# complete.net
KiCad netlist of a schematic drawn in EAGLE
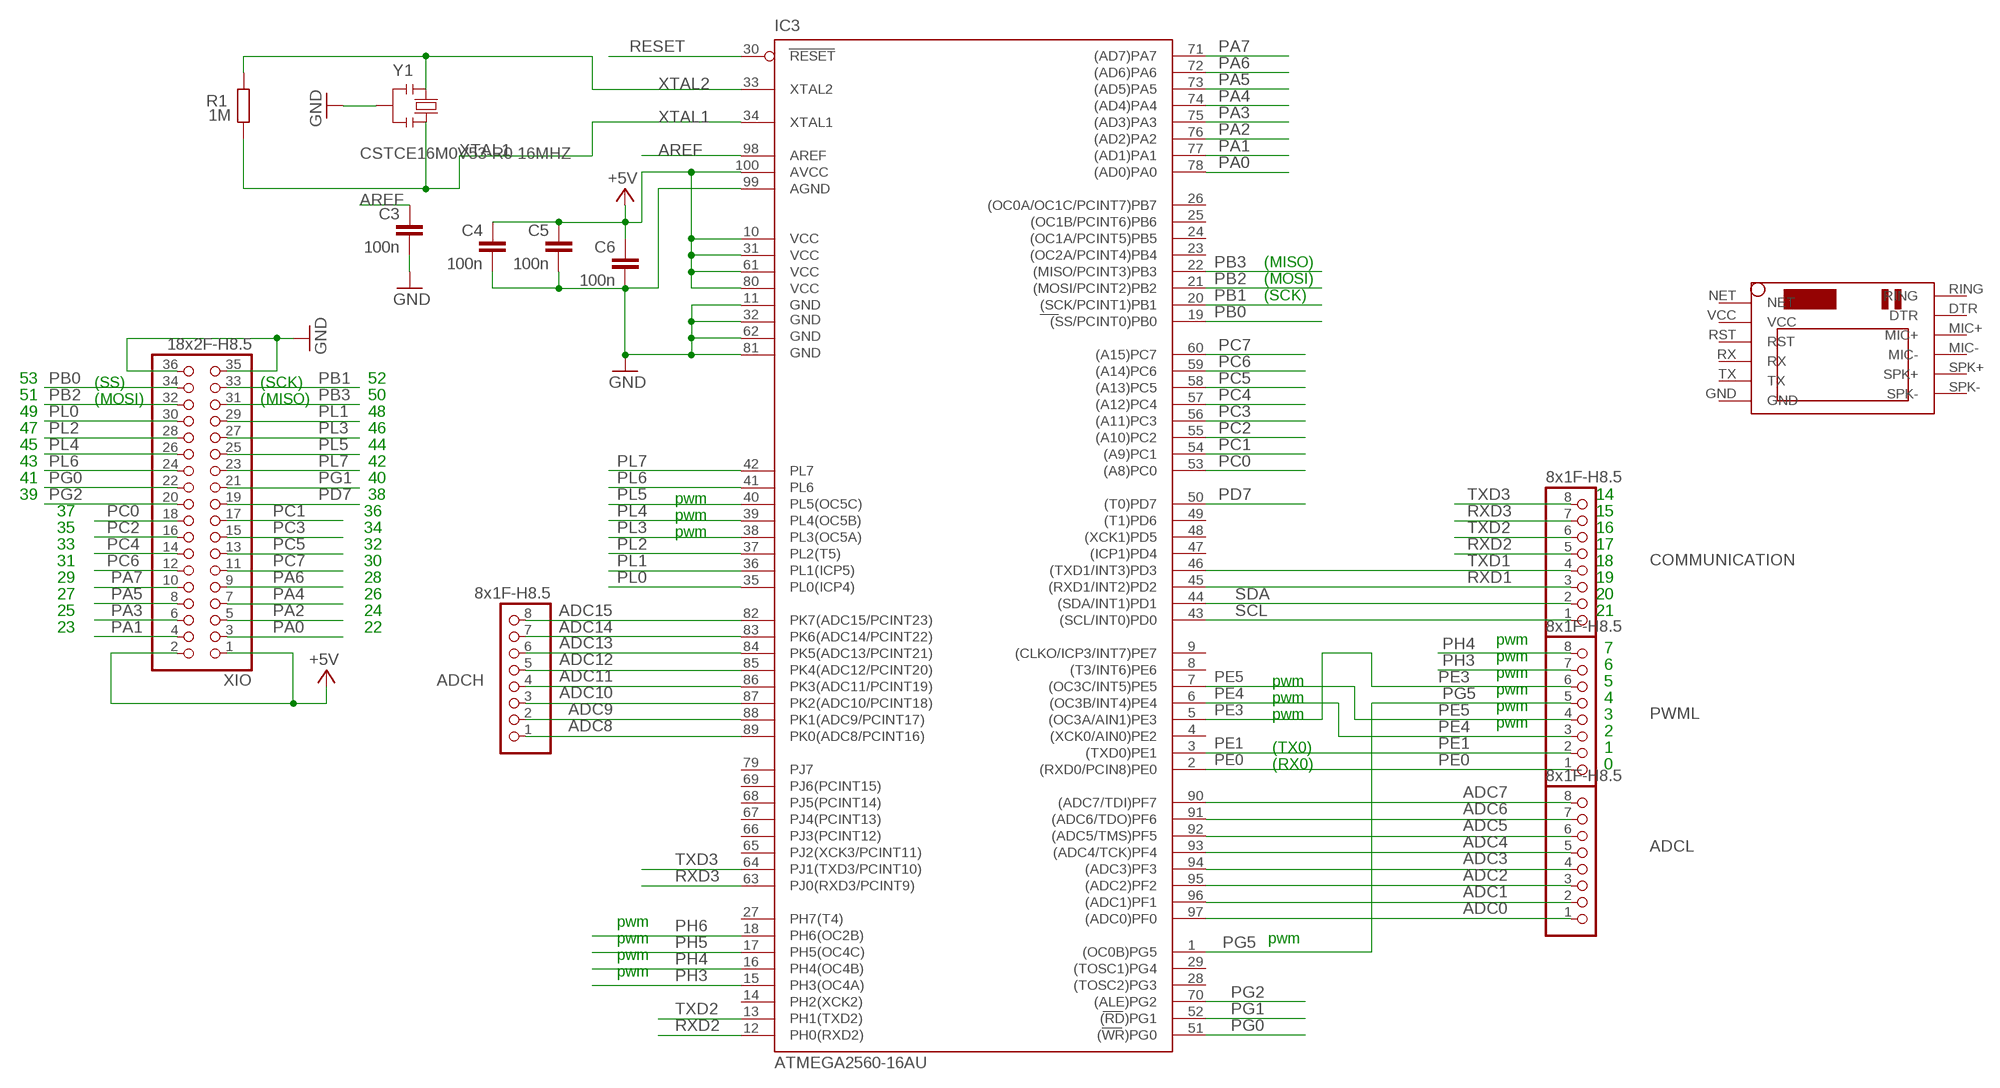
[diagram p0: schematic, sheet 1]

(export (version "E")
  (design (tool "Eeschema 10.0.6"))
  (components
    (comp (ref "ADCH")
      (value "8x1F-H8.5")
      (footprint "eagle-import:1X08")
      (libsource (lib "eagle-import") (part "PINHD-1X8"))
    )
    (comp (ref "ADCL")
      (value "8x1F-H8.5")
      (footprint "eagle-import:1X08")
      (libsource (lib "eagle-import") (part "PINHD-1X8"))
    )
    (comp (ref "C3")
      (value "100n")
      (footprint "eagle-import:C0603-ROUND")
      (libsource (lib "eagle-import") (part "C-EU0603-RND"))
    )
    (comp (ref "C4")
      (value "100n")
      (footprint "eagle-import:C0603-ROUND")
      (libsource (lib "eagle-import") (part "C-EU0603-RND"))
    )
    (comp (ref "C5")
      (value "100n")
      (footprint "eagle-import:C0603-ROUND")
      (libsource (lib "eagle-import") (part "C-EU0603-RND"))
    )
    (comp (ref "C6")
      (value "100n")
      (footprint "eagle-import:C0603-ROUND")
      (libsource (lib "eagle-import") (part "C-EU0603-RND"))
    )
    (comp (ref "COMMUNICATION")
      (value "8x1F-H8.5")
      (footprint "eagle-import:1X08")
      (libsource (lib "eagle-import") (part "PINHD-1X8"))
    )
    (comp (ref "IC3")
      (value "ATMEGA2560-16AU")
      (footprint "eagle-import:TQFP100")
      (libsource (lib "eagle-import") (part "ATMEGA2560AU2560-16"))
    )
    (comp (ref "PWML")
      (value "8x1F-H8.5")
      (footprint "eagle-import:1X08")
      (libsource (lib "eagle-import") (part "PINHD-1X8"))
    )
    (comp (ref "R1")
      (value "1M")
      (footprint "eagle-import:R0603-ROUND")
      (libsource (lib "eagle-import") (part "R-EU_R0603"))
    )
    (comp (ref "U$1")
      (value "SIM800LMODULE")
      (footprint "eagle-import:SIM800LMODULE")
      (libsource (lib "eagle-import") (part "SIM800LMODULE"))
    )
    (comp (ref "XIO")
      (value "18x2F-H8.5")
      (footprint "eagle-import:2X18")
      (libsource (lib "eagle-import") (part "PINHD-2X18"))
    )
    (comp (ref "Y1")
      (value "CSTCE16M0V53-R0 16MHZ")
      (footprint "eagle-import:RESONATOR")
      (libsource (lib "eagle-import") (part "RESONATORMU"))
    )
  )
  (nets
    (net (code "1") (name "+5V") (class "Default")
      (node (ref "C4") (pin "1") (pinfunction "1_1") (pintype "passive"))
      (node (ref "C5") (pin "1") (pinfunction "1_1") (pintype "passive"))
      (node (ref "C6") (pin "1") (pinfunction "1_1") (pintype "passive"))
      (node (ref "IC3") (pin "10") (pinfunction "VCC_10") (pintype "power_in"))
      (node (ref "IC3") (pin "100") (pinfunction "AVCC_100") (pintype "power_in"))
      (node (ref "IC3") (pin "31") (pinfunction "VCC1_31") (pintype "power_in"))
      (node (ref "IC3") (pin "61") (pinfunction "VCC2_61") (pintype "power_in"))
      (node (ref "IC3") (pin "80") (pinfunction "VCC3_80") (pintype "power_in"))
      (node (ref "XIO") (pin "1") (pinfunction "1_1") (pintype "passive"))
      (node (ref "XIO") (pin "2") (pinfunction "2_2") (pintype "passive"))
    )
    (net (code "2") (name "/ADC0") (class "Default")
      (node (ref "ADCL") (pin "1") (pinfunction "1_1") (pintype "passive"))
      (node (ref "IC3") (pin "97") (pinfunction "(ADC0)PF0_97") (pintype "bidirectional"))
    )
    (net (code "3") (name "/ADC1") (class "Default")
      (node (ref "ADCL") (pin "2") (pinfunction "2_2") (pintype "passive"))
      (node (ref "IC3") (pin "96") (pinfunction "(ADC1)PF1_96") (pintype "bidirectional"))
    )
    (net (code "4") (name "/ADC2") (class "Default")
      (node (ref "ADCL") (pin "3") (pinfunction "3_3") (pintype "passive"))
      (node (ref "IC3") (pin "95") (pinfunction "(ADC2)PF2_95") (pintype "bidirectional"))
    )
    (net (code "5") (name "/ADC3") (class "Default")
      (node (ref "ADCL") (pin "4") (pinfunction "4_4") (pintype "passive"))
      (node (ref "IC3") (pin "94") (pinfunction "(ADC3)PF3_94") (pintype "bidirectional"))
    )
    (net (code "6") (name "/ADC4") (class "Default")
      (node (ref "ADCL") (pin "5") (pinfunction "5_5") (pintype "passive"))
      (node (ref "IC3") (pin "93") (pinfunction "(ADC4/TCK)PF4_93") (pintype "bidirectional"))
    )
    (net (code "7") (name "/ADC5") (class "Default")
      (node (ref "ADCL") (pin "6") (pinfunction "6_6") (pintype "passive"))
      (node (ref "IC3") (pin "92") (pinfunction "(ADC5/TMS)PF5_92") (pintype "bidirectional"))
    )
    (net (code "8") (name "/ADC6") (class "Default")
      (node (ref "ADCL") (pin "7") (pinfunction "7_7") (pintype "passive"))
      (node (ref "IC3") (pin "91") (pinfunction "(ADC6/TDO)PF6_91") (pintype "bidirectional"))
    )
    (net (code "9") (name "/ADC7") (class "Default")
      (node (ref "ADCL") (pin "8") (pinfunction "8_8") (pintype "passive"))
      (node (ref "IC3") (pin "90") (pinfunction "(ADC7/TDI)PF7_90") (pintype "bidirectional"))
    )
    (net (code "10") (name "/ADC8") (class "Default")
      (node (ref "ADCH") (pin "1") (pinfunction "1_1") (pintype "passive"))
      (node (ref "IC3") (pin "89") (pinfunction "PK0(ADC8/PCINT16)_89") (pintype "bidirectional"))
    )
    (net (code "11") (name "/ADC9") (class "Default")
      (node (ref "ADCH") (pin "2") (pinfunction "2_2") (pintype "passive"))
      (node (ref "IC3") (pin "88") (pinfunction "PK1(ADC9/PCINT17)_88") (pintype "bidirectional"))
    )
    (net (code "12") (name "/ADC10") (class "Default")
      (node (ref "ADCH") (pin "3") (pinfunction "3_3") (pintype "passive"))
      (node (ref "IC3") (pin "87") (pinfunction "PK2(ADC10/PCINT18)_87") (pintype "bidirectional"))
    )
    (net (code "13") (name "/ADC11") (class "Default")
      (node (ref "ADCH") (pin "4") (pinfunction "4_4") (pintype "passive"))
      (node (ref "IC3") (pin "86") (pinfunction "PK3(ADC11/PCINT19)_86") (pintype "bidirectional"))
    )
    (net (code "14") (name "/ADC12") (class "Default")
      (node (ref "ADCH") (pin "5") (pinfunction "5_5") (pintype "passive"))
      (node (ref "IC3") (pin "85") (pinfunction "PK4(ADC12/PCINT20)_85") (pintype "bidirectional"))
    )
    (net (code "15") (name "/ADC13") (class "Default")
      (node (ref "ADCH") (pin "6") (pinfunction "6_6") (pintype "passive"))
      (node (ref "IC3") (pin "84") (pinfunction "PK5(ADC13/PCINT21)_84") (pintype "bidirectional"))
    )
    (net (code "16") (name "/ADC14") (class "Default")
      (node (ref "ADCH") (pin "7") (pinfunction "7_7") (pintype "passive"))
      (node (ref "IC3") (pin "83") (pinfunction "PK6(ADC14/PCINT22)_83") (pintype "bidirectional"))
    )
    (net (code "17") (name "/ADC15") (class "Default")
      (node (ref "ADCH") (pin "8") (pinfunction "8_8") (pintype "passive"))
      (node (ref "IC3") (pin "82") (pinfunction "PK7(ADC15/PCINT23)_82") (pintype "bidirectional"))
    )
    (net (code "18") (name "/AREF") (class "Default")
      (node (ref "C3") (pin "1") (pinfunction "1_1") (pintype "passive"))
      (node (ref "IC3") (pin "98") (pinfunction "AREF_98") (pintype "bidirectional"))
    )
    (net (code "19") (name "/PA0") (class "Default")
      (node (ref "IC3") (pin "78") (pinfunction "(AD0)PA0_78") (pintype "bidirectional"))
      (node (ref "XIO") (pin "3") (pinfunction "3_3") (pintype "passive"))
    )
    (net (code "20") (name "/PA1") (class "Default")
      (node (ref "IC3") (pin "77") (pinfunction "(AD1)PA1_77") (pintype "bidirectional"))
      (node (ref "XIO") (pin "4") (pinfunction "4_4") (pintype "passive"))
    )
    (net (code "21") (name "/PA2") (class "Default")
      (node (ref "IC3") (pin "76") (pinfunction "(AD2)PA2_76") (pintype "bidirectional"))
      (node (ref "XIO") (pin "5") (pinfunction "5_5") (pintype "passive"))
    )
    (net (code "22") (name "/PA3") (class "Default")
      (node (ref "IC3") (pin "75") (pinfunction "(AD3)PA3_75") (pintype "bidirectional"))
      (node (ref "XIO") (pin "6") (pinfunction "6_6") (pintype "passive"))
    )
    (net (code "23") (name "/PA4") (class "Default")
      (node (ref "IC3") (pin "74") (pinfunction "(AD4)PA4_74") (pintype "bidirectional"))
      (node (ref "XIO") (pin "7") (pinfunction "7_7") (pintype "passive"))
    )
    (net (code "24") (name "/PA5") (class "Default")
      (node (ref "IC3") (pin "73") (pinfunction "(AD5)PA5_73") (pintype "bidirectional"))
      (node (ref "XIO") (pin "8") (pinfunction "8_8") (pintype "passive"))
    )
    (net (code "25") (name "/PA6") (class "Default")
      (node (ref "IC3") (pin "72") (pinfunction "(AD6)PA6_72") (pintype "bidirectional"))
      (node (ref "XIO") (pin "9") (pinfunction "9_9") (pintype "passive"))
    )
    (net (code "26") (name "/PA7") (class "Default")
      (node (ref "IC3") (pin "71") (pinfunction "(AD7)PA7_71") (pintype "bidirectional"))
      (node (ref "XIO") (pin "10") (pinfunction "10_10") (pintype "passive"))
    )
    (net (code "27") (name "/PB0") (class "Default")
      (node (ref "IC3") (pin "19") (pinfunction "(SS/PCINT0)PB0_19") (pintype "bidirectional"))
      (node (ref "XIO") (pin "34") (pinfunction "34_34") (pintype "passive"))
    )
    (net (code "28") (name "/PB1") (class "Default")
      (node (ref "IC3") (pin "20") (pinfunction "(SCK/PCINT1)PB1_20") (pintype "bidirectional"))
      (node (ref "XIO") (pin "33") (pinfunction "33_33") (pintype "passive"))
    )
    (net (code "29") (name "/PB2") (class "Default")
      (node (ref "IC3") (pin "21") (pinfunction "(MOSI/PCINT2)PB2_21") (pintype "bidirectional"))
      (node (ref "XIO") (pin "32") (pinfunction "32_32") (pintype "passive"))
    )
    (net (code "30") (name "/PB3") (class "Default")
      (node (ref "IC3") (pin "22") (pinfunction "(MISO/PCINT3)PB3_22") (pintype "bidirectional"))
      (node (ref "XIO") (pin "31") (pinfunction "31_31") (pintype "passive"))
    )
    (net (code "31") (name "/PC0") (class "Default")
      (node (ref "IC3") (pin "53") (pinfunction "(A8)PC0_53") (pintype "bidirectional"))
      (node (ref "XIO") (pin "18") (pinfunction "18_18") (pintype "passive"))
    )
    (net (code "32") (name "/PC1") (class "Default")
      (node (ref "IC3") (pin "54") (pinfunction "(A9)PC1_54") (pintype "bidirectional"))
      (node (ref "XIO") (pin "17") (pinfunction "17_17") (pintype "passive"))
    )
    (net (code "33") (name "/PC2") (class "Default")
      (node (ref "IC3") (pin "55") (pinfunction "(A10)PC2_55") (pintype "bidirectional"))
      (node (ref "XIO") (pin "16") (pinfunction "16_16") (pintype "passive"))
    )
    (net (code "34") (name "/PC3") (class "Default")
      (node (ref "IC3") (pin "56") (pinfunction "(A11)PC3_56") (pintype "bidirectional"))
      (node (ref "XIO") (pin "15") (pinfunction "15_15") (pintype "passive"))
    )
    (net (code "35") (name "/PC4") (class "Default")
      (node (ref "IC3") (pin "57") (pinfunction "(A12)PC4_57") (pintype "bidirectional"))
      (node (ref "XIO") (pin "14") (pinfunction "14_14") (pintype "passive"))
    )
    (net (code "36") (name "/PC5") (class "Default")
      (node (ref "IC3") (pin "58") (pinfunction "(A13)PC5_58") (pintype "bidirectional"))
      (node (ref "XIO") (pin "13") (pinfunction "13_13") (pintype "passive"))
    )
    (net (code "37") (name "/PC6") (class "Default")
      (node (ref "IC3") (pin "59") (pinfunction "(A14)PC6_59") (pintype "bidirectional"))
      (node (ref "XIO") (pin "12") (pinfunction "12_12") (pintype "passive"))
    )
    (net (code "38") (name "/PC7") (class "Default")
      (node (ref "IC3") (pin "60") (pinfunction "(A15)PC7_60") (pintype "bidirectional"))
      (node (ref "XIO") (pin "11") (pinfunction "11_11") (pintype "passive"))
    )
    (net (code "39") (name "/PD7") (class "Default")
      (node (ref "IC3") (pin "50") (pinfunction "(T0)PD7_50") (pintype "bidirectional"))
      (node (ref "XIO") (pin "19") (pinfunction "19_19") (pintype "passive"))
    )
    (net (code "40") (name "/PE0") (class "Default")
      (node (ref "IC3") (pin "2") (pinfunction "(RXD0/PCIN8)PE0_2") (pintype "bidirectional"))
      (node (ref "PWML") (pin "1") (pinfunction "1_1") (pintype "passive"))
    )
    (net (code "41") (name "/PE1") (class "Default")
      (node (ref "IC3") (pin "3") (pinfunction "(TXD0)PE1_3") (pintype "bidirectional"))
      (node (ref "PWML") (pin "2") (pinfunction "2_2") (pintype "passive"))
    )
    (net (code "42") (name "/PE3") (class "Default")
      (node (ref "IC3") (pin "5") (pinfunction "(OC3A/AIN1)PE3_5") (pintype "bidirectional"))
      (node (ref "PWML") (pin "6") (pinfunction "6_6") (pintype "passive"))
    )
    (net (code "43") (name "/PE4") (class "Default")
      (node (ref "IC3") (pin "6") (pinfunction "(OC3B/INT4)PE4_6") (pintype "bidirectional"))
      (node (ref "PWML") (pin "3") (pinfunction "3_3") (pintype "passive"))
    )
    (net (code "44") (name "/PE5") (class "Default")
      (node (ref "IC3") (pin "7") (pinfunction "(OC3C/INT5)PE5_7") (pintype "bidirectional"))
      (node (ref "PWML") (pin "4") (pinfunction "4_4") (pintype "passive"))
    )
    (net (code "45") (name "/PG0") (class "Default")
      (node (ref "IC3") (pin "51") (pinfunction "(WR)PG0_51") (pintype "bidirectional"))
      (node (ref "XIO") (pin "22") (pinfunction "22_22") (pintype "passive"))
    )
    (net (code "46") (name "/PG1") (class "Default")
      (node (ref "IC3") (pin "52") (pinfunction "(RD)PG1_52") (pintype "bidirectional"))
      (node (ref "XIO") (pin "21") (pinfunction "21_21") (pintype "passive"))
    )
    (net (code "47") (name "/PG2") (class "Default")
      (node (ref "IC3") (pin "70") (pinfunction "(ALE)PG2_70") (pintype "bidirectional"))
      (node (ref "XIO") (pin "20") (pinfunction "20_20") (pintype "passive"))
    )
    (net (code "48") (name "/PG5") (class "Default")
      (node (ref "IC3") (pin "1") (pinfunction "(OC0B)PG5_1") (pintype "bidirectional"))
      (node (ref "PWML") (pin "5") (pinfunction "5_5") (pintype "passive"))
    )
    (net (code "49") (name "/PH3") (class "Default")
      (node (ref "IC3") (pin "15") (pinfunction "PH3(OC4A)_15") (pintype "bidirectional"))
      (node (ref "PWML") (pin "7") (pinfunction "7_7") (pintype "passive"))
    )
    (net (code "50") (name "/PH4") (class "Default")
      (node (ref "IC3") (pin "16") (pinfunction "PH4(OC4B)_16") (pintype "bidirectional"))
      (node (ref "PWML") (pin "8") (pinfunction "8_8") (pintype "passive"))
    )
    (net (code "51") (name "/PH5") (class "Default")
      (node (ref "IC3") (pin "17") (pinfunction "PH5(OC4C)_17") (pintype "bidirectional"))
    )
    (net (code "52") (name "/PH6") (class "Default")
      (node (ref "IC3") (pin "18") (pinfunction "PH6(OC2B)_18") (pintype "bidirectional"))
    )
    (net (code "53") (name "/PL0") (class "Default")
      (node (ref "IC3") (pin "35") (pinfunction "PL0(ICP4)_35") (pintype "bidirectional"))
      (node (ref "XIO") (pin "30") (pinfunction "30_30") (pintype "passive"))
    )
    (net (code "54") (name "/PL1") (class "Default")
      (node (ref "IC3") (pin "36") (pinfunction "PL1(ICP5)_36") (pintype "bidirectional"))
      (node (ref "XIO") (pin "29") (pinfunction "29_29") (pintype "passive"))
    )
    (net (code "55") (name "/PL2") (class "Default")
      (node (ref "IC3") (pin "37") (pinfunction "PL2(T5)_37") (pintype "bidirectional"))
      (node (ref "XIO") (pin "28") (pinfunction "28_28") (pintype "passive"))
    )
    (net (code "56") (name "/PL3") (class "Default")
      (node (ref "IC3") (pin "38") (pinfunction "PL3(OC5A)_38") (pintype "bidirectional"))
      (node (ref "XIO") (pin "27") (pinfunction "27_27") (pintype "passive"))
    )
    (net (code "57") (name "/PL4") (class "Default")
      (node (ref "IC3") (pin "39") (pinfunction "PL4(OC5B)_39") (pintype "bidirectional"))
      (node (ref "XIO") (pin "26") (pinfunction "26_26") (pintype "passive"))
    )
    (net (code "58") (name "/PL5") (class "Default")
      (node (ref "IC3") (pin "40") (pinfunction "PL5(OC5C)_40") (pintype "bidirectional"))
      (node (ref "XIO") (pin "25") (pinfunction "25_25") (pintype "passive"))
    )
    (net (code "59") (name "/PL6") (class "Default")
      (node (ref "IC3") (pin "41") (pinfunction "PL6_41") (pintype "bidirectional"))
      (node (ref "XIO") (pin "24") (pinfunction "24_24") (pintype "passive"))
    )
    (net (code "60") (name "/PL7") (class "Default")
      (node (ref "IC3") (pin "42") (pinfunction "PL7_42") (pintype "bidirectional"))
      (node (ref "XIO") (pin "23") (pinfunction "23_23") (pintype "passive"))
    )
    (net (code "61") (name "/RESET") (class "Default")
      (node (ref "IC3") (pin "30") (pinfunction "RESET_30") (pintype "input"))
    )
    (net (code "62") (name "/RXD1") (class "Default")
      (node (ref "COMMUNICATION") (pin "3") (pinfunction "3_3") (pintype "passive"))
      (node (ref "IC3") (pin "45") (pinfunction "(RXD1/INT2)PD2_45") (pintype "bidirectional"))
    )
    (net (code "63") (name "/RXD2") (class "Default")
      (node (ref "COMMUNICATION") (pin "5") (pinfunction "5_5") (pintype "passive"))
      (node (ref "IC3") (pin "12") (pinfunction "PH0(RXD2)_12") (pintype "bidirectional"))
    )
    (net (code "64") (name "/RXD3") (class "Default")
      (node (ref "COMMUNICATION") (pin "7") (pinfunction "7_7") (pintype "passive"))
      (node (ref "IC3") (pin "63") (pinfunction "PJ0(RXD3/PCINT9)_63") (pintype "bidirectional"))
    )
    (net (code "65") (name "/SCL") (class "Default")
      (node (ref "COMMUNICATION") (pin "1") (pinfunction "1_1") (pintype "passive"))
      (node (ref "IC3") (pin "43") (pinfunction "(SCL/INT0)PD0_43") (pintype "bidirectional"))
    )
    (net (code "66") (name "/SDA") (class "Default")
      (node (ref "COMMUNICATION") (pin "2") (pinfunction "2_2") (pintype "passive"))
      (node (ref "IC3") (pin "44") (pinfunction "(SDA/INT1)PD1_44") (pintype "bidirectional"))
    )
    (net (code "67") (name "/TXD1") (class "Default")
      (node (ref "COMMUNICATION") (pin "4") (pinfunction "4_4") (pintype "passive"))
      (node (ref "IC3") (pin "46") (pinfunction "(TXD1/INT3)PD3_46") (pintype "bidirectional"))
    )
    (net (code "68") (name "/TXD2") (class "Default")
      (node (ref "COMMUNICATION") (pin "6") (pinfunction "6_6") (pintype "passive"))
      (node (ref "IC3") (pin "13") (pinfunction "PH1(TXD2)_13") (pintype "bidirectional"))
    )
    (net (code "69") (name "/TXD3") (class "Default")
      (node (ref "COMMUNICATION") (pin "8") (pinfunction "8_8") (pintype "passive"))
      (node (ref "IC3") (pin "64") (pinfunction "PJ1(TXD3/PCINT10)_64") (pintype "bidirectional"))
    )
    (net (code "70") (name "/XTAL1") (class "Default")
      (node (ref "IC3") (pin "34") (pinfunction "XTAL1_34") (pintype "input"))
      (node (ref "R1") (pin "1") (pinfunction "1_1") (pintype "passive"))
      (node (ref "Y1") (pin "3") (pinfunction "3_3") (pintype "passive"))
    )
    (net (code "71") (name "/XTAL2") (class "Default")
      (node (ref "IC3") (pin "33") (pinfunction "XTAL2_33") (pintype "output"))
      (node (ref "R1") (pin "2") (pinfunction "2_2") (pintype "passive"))
      (node (ref "Y1") (pin "1") (pinfunction "1_1") (pintype "passive"))
    )
    (net (code "72") (name "GND") (class "Default")
      (node (ref "C3") (pin "2") (pinfunction "2_2") (pintype "passive"))
      (node (ref "C4") (pin "2") (pinfunction "2_2") (pintype "passive"))
      (node (ref "C5") (pin "2") (pinfunction "2_2") (pintype "passive"))
      (node (ref "C6") (pin "2") (pinfunction "2_2") (pintype "passive"))
      (node (ref "IC3") (pin "11") (pinfunction "GND_11") (pintype "power_in"))
      (node (ref "IC3") (pin "32") (pinfunction "GND1_32") (pintype "power_in"))
      (node (ref "IC3") (pin "62") (pinfunction "GND2_62") (pintype "power_in"))
      (node (ref "IC3") (pin "81") (pinfunction "GND3_81") (pintype "power_in"))
      (node (ref "IC3") (pin "99") (pinfunction "AGND_99") (pintype "power_in"))
      (node (ref "XIO") (pin "35") (pinfunction "35_35") (pintype "passive"))
      (node (ref "XIO") (pin "36") (pinfunction "36_36") (pintype "passive"))
      (node (ref "Y1") (pin "2") (pinfunction "2_2") (pintype "passive"))
    )
    (net (code "73") (name "unconnected-(IC3-(CLKO{slash}ICP3{slash}INT7)PE7-Pad9)") (class "Default")
      (node (ref "IC3") (pin "9") (pinfunction "(CLKO/ICP3/INT7)PE7_9") (pintype "bidirectional"))
    )
    (net (code "74") (name "unconnected-(IC3-(ICP1)PD4-Pad47)") (class "Default")
      (node (ref "IC3") (pin "47") (pinfunction "(ICP1)PD4_47") (pintype "bidirectional"))
    )
    (net (code "75") (name "unconnected-(IC3-(OC0A{slash}OC1C{slash}PCINT7)PB7-Pad26)") (class "Default")
      (node (ref "IC3") (pin "26") (pinfunction "(OC0A/OC1C/PCINT7)PB7_26") (pintype "bidirectional"))
    )
    (net (code "76") (name "unconnected-(IC3-(OC1A{slash}PCINT5)PB5-Pad24)") (class "Default")
      (node (ref "IC3") (pin "24") (pinfunction "(OC1A/PCINT5)PB5_24") (pintype "bidirectional"))
    )
    (net (code "77") (name "unconnected-(IC3-(OC1B{slash}PCINT6)PB6-Pad25)") (class "Default")
      (node (ref "IC3") (pin "25") (pinfunction "(OC1B/PCINT6)PB6_25") (pintype "bidirectional"))
    )
    (net (code "78") (name "unconnected-(IC3-(OC2A{slash}PCINT4)PB4-Pad23)") (class "Default")
      (node (ref "IC3") (pin "23") (pinfunction "(OC2A/PCINT4)PB4_23") (pintype "bidirectional"))
    )
    (net (code "79") (name "unconnected-(IC3-(T1)PD6-Pad49)") (class "Default")
      (node (ref "IC3") (pin "49") (pinfunction "(T1)PD6_49") (pintype "bidirectional"))
    )
    (net (code "80") (name "unconnected-(IC3-(T3{slash}INT6)PE6-Pad8)") (class "Default")
      (node (ref "IC3") (pin "8") (pinfunction "(T3/INT6)PE6_8") (pintype "bidirectional"))
    )
    (net (code "81") (name "unconnected-(IC3-(TOSC1)PG4-Pad29)") (class "Default")
      (node (ref "IC3") (pin "29") (pinfunction "(TOSC1)PG4_29") (pintype "bidirectional"))
    )
    (net (code "82") (name "unconnected-(IC3-(TOSC2)PG3-Pad28)") (class "Default")
      (node (ref "IC3") (pin "28") (pinfunction "(TOSC2)PG3_28") (pintype "bidirectional"))
    )
    (net (code "83") (name "unconnected-(IC3-(XCK0{slash}AIN0)PE2-Pad4)") (class "Default")
      (node (ref "IC3") (pin "4") (pinfunction "(XCK0/AIN0)PE2_4") (pintype "bidirectional"))
    )
    (net (code "84") (name "unconnected-(IC3-(XCK1)PD5-Pad48)") (class "Default")
      (node (ref "IC3") (pin "48") (pinfunction "(XCK1)PD5_48") (pintype "bidirectional"))
    )
    (net (code "85") (name "unconnected-(IC3-PH2(XCK2)-Pad14)") (class "Default")
      (node (ref "IC3") (pin "14") (pinfunction "PH2(XCK2)_14") (pintype "bidirectional"))
    )
    (net (code "86") (name "unconnected-(IC3-PH7(T4)-Pad27)") (class "Default")
      (node (ref "IC3") (pin "27") (pinfunction "PH7(T4)_27") (pintype "bidirectional"))
    )
    (net (code "87") (name "unconnected-(IC3-PJ2(XCK3{slash}PCINT11)-Pad65)") (class "Default")
      (node (ref "IC3") (pin "65") (pinfunction "PJ2(XCK3/PCINT11)_65") (pintype "bidirectional"))
    )
    (net (code "88") (name "unconnected-(IC3-PJ3(PCINT12)-Pad66)") (class "Default")
      (node (ref "IC3") (pin "66") (pinfunction "PJ3(PCINT12)_66") (pintype "bidirectional"))
    )
    (net (code "89") (name "unconnected-(IC3-PJ4(PCINT13)-Pad67)") (class "Default")
      (node (ref "IC3") (pin "67") (pinfunction "PJ4(PCINT13)_67") (pintype "bidirectional"))
    )
    (net (code "90") (name "unconnected-(IC3-PJ5(PCINT14)-Pad68)") (class "Default")
      (node (ref "IC3") (pin "68") (pinfunction "PJ5(PCINT14)_68") (pintype "bidirectional"))
    )
    (net (code "91") (name "unconnected-(IC3-PJ6(PCINT15)-Pad69)") (class "Default")
      (node (ref "IC3") (pin "69") (pinfunction "PJ6(PCINT15)_69") (pintype "bidirectional"))
    )
    (net (code "92") (name "unconnected-(IC3-PJ7-Pad79)") (class "Default")
      (node (ref "IC3") (pin "79") (pinfunction "PJ7_79") (pintype "bidirectional"))
    )
    (net (code "93") (name "unconnected-(U$1-PadDTR)") (class "Default")
      (node (ref "U$1") (pin "DTR") (pinfunction "DTR_DTR") (pintype "bidirectional"))
    )
    (net (code "94") (name "unconnected-(U$1-PadGND)") (class "Default")
      (node (ref "U$1") (pin "GND") (pinfunction "GND_GND") (pintype "bidirectional"))
    )
    (net (code "95") (name "unconnected-(U$1-PadMIC+)") (class "Default")
      (node (ref "U$1") (pin "MIC+") (pinfunction "MIC+_MIC+") (pintype "bidirectional"))
    )
    (net (code "96") (name "unconnected-(U$1-PadMIC-)") (class "Default")
      (node (ref "U$1") (pin "MIC-") (pinfunction "MIC-_MIC-") (pintype "bidirectional"))
    )
    (net (code "97") (name "unconnected-(U$1-PadNET)") (class "Default")
      (node (ref "U$1") (pin "NET") (pinfunction "NET_NET") (pintype "bidirectional"))
    )
    (net (code "98") (name "unconnected-(U$1-PadRING)") (class "Default")
      (node (ref "U$1") (pin "RING") (pinfunction "RING_RING") (pintype "bidirectional"))
    )
    (net (code "99") (name "unconnected-(U$1-PadRST)") (class "Default")
      (node (ref "U$1") (pin "RST") (pinfunction "RST_RST") (pintype "bidirectional"))
    )
    (net (code "100") (name "unconnected-(U$1-PadRX)") (class "Default")
      (node (ref "U$1") (pin "RX") (pinfunction "RX_RX") (pintype "bidirectional"))
    )
    (net (code "101") (name "unconnected-(U$1-PadSPK+)") (class "Default")
      (node (ref "U$1") (pin "SPK+") (pinfunction "SPK+_SPK+") (pintype "bidirectional"))
    )
    (net (code "102") (name "unconnected-(U$1-PadSPK-)") (class "Default")
      (node (ref "U$1") (pin "SPK-") (pinfunction "SPK-_SPK-") (pintype "bidirectional"))
    )
    (net (code "103") (name "unconnected-(U$1-PadTX)") (class "Default")
      (node (ref "U$1") (pin "TX") (pinfunction "TX_TX") (pintype "bidirectional"))
    )
    (net (code "104") (name "unconnected-(U$1-PadVCC)") (class "Default")
      (node (ref "U$1") (pin "VCC") (pinfunction "VCC_VCC") (pintype "bidirectional"))
    )
  )
)
